# main.net
KiCad netlist of a schematic drawn in EAGLE
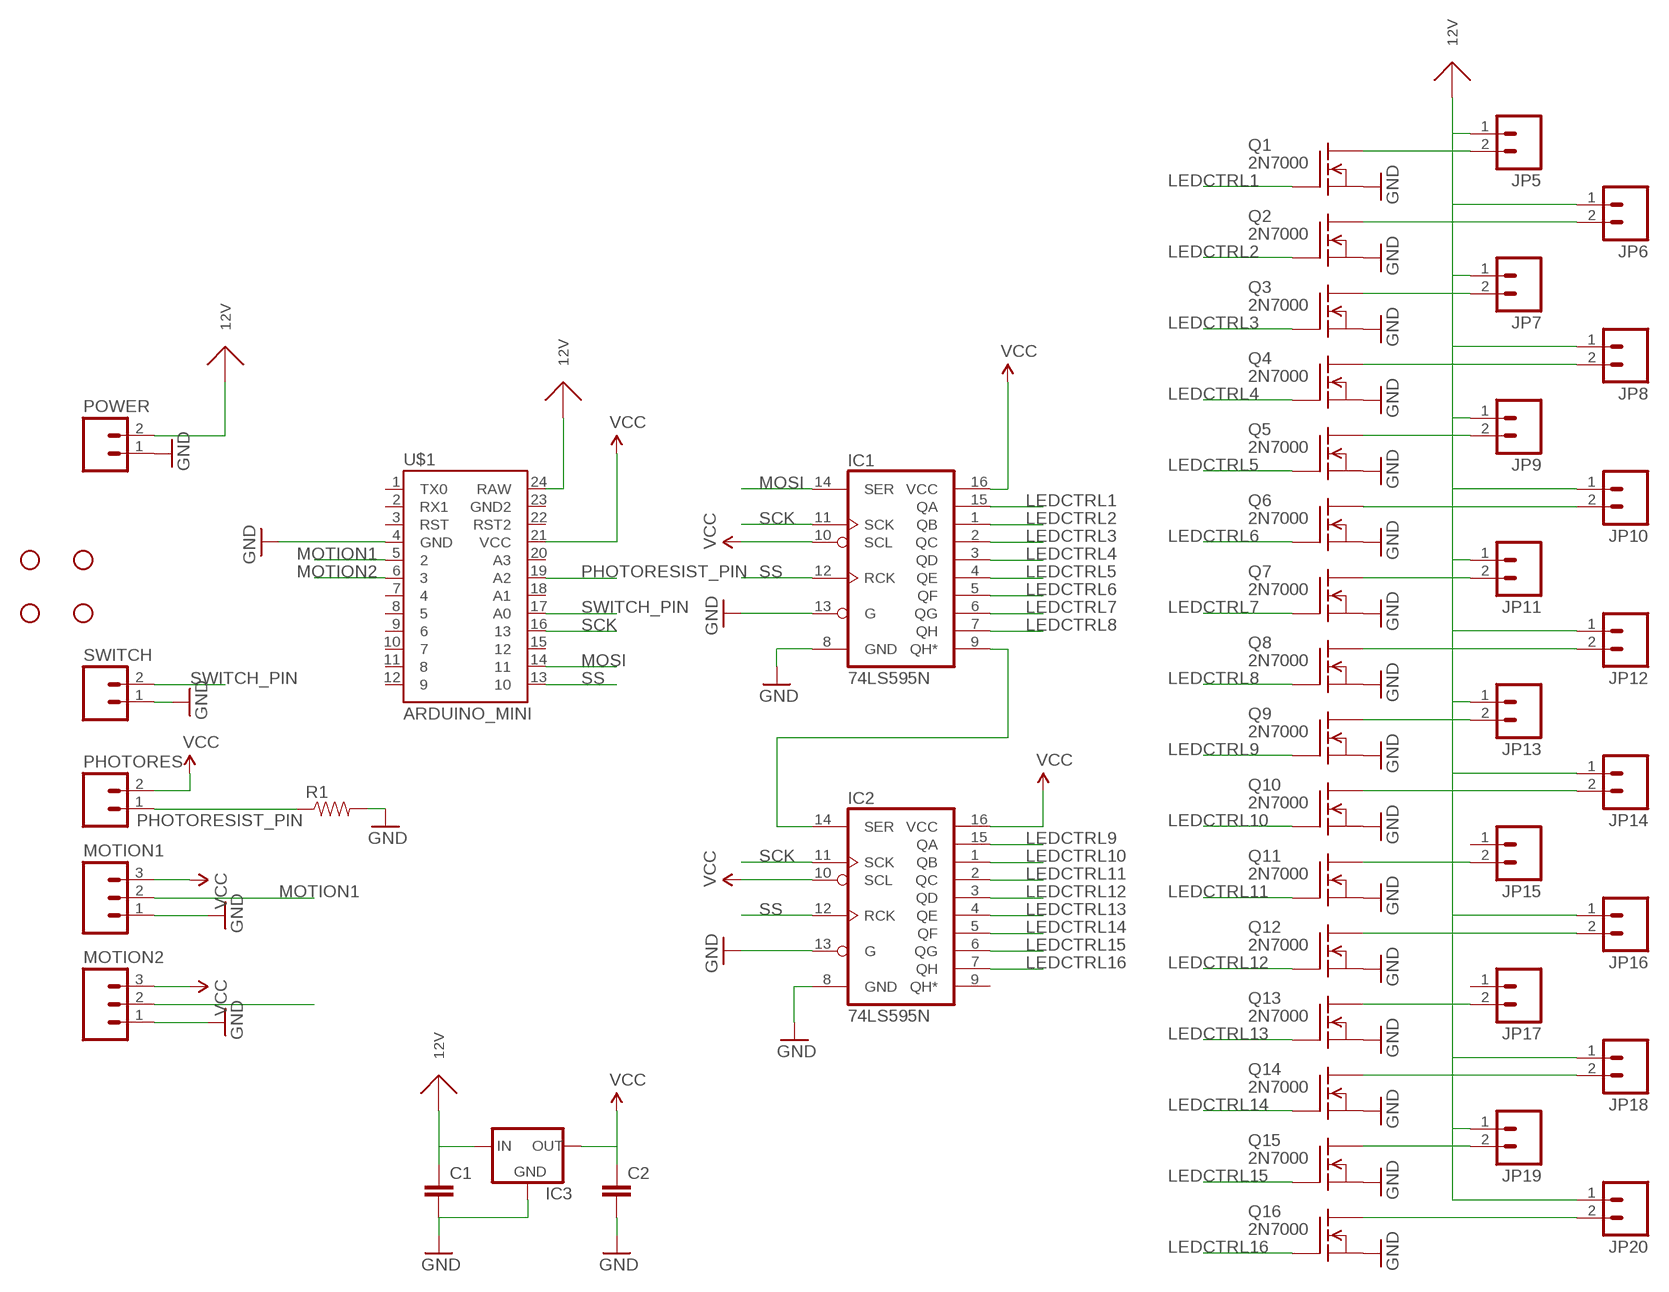
[diagram p0: schematic, sheet 1]

(export (version "E")
  (design (tool "Eeschema 10.0.6"))
  (components
    (comp (ref "C1")
      (value "CAPKIT")
      (footprint "eagle-import:CAP-PTH-SMALL-KIT")
      (libsource (lib "eagle-import") (part "CAPKIT"))
    )
    (comp (ref "C2")
      (value "CAPKIT")
      (footprint "eagle-import:CAP-PTH-SMALL-KIT")
      (libsource (lib "eagle-import") (part "CAPKIT"))
    )
    (comp (ref "IC1")
      (value "74LS595N")
      (footprint "eagle-import:DIL16")
      (libsource (lib "eagle-import") (part "74595NLS"))
    )
    (comp (ref "IC2")
      (value "74LS595N")
      (footprint "eagle-import:DIL16")
      (libsource (lib "eagle-import") (part "74595NLS"))
    )
    (comp (ref "IC3")
      (value "V_REG_78XXSINK")
      (footprint "eagle-import:TO220-IGO")
      (libsource (lib "eagle-import") (part "V_REG_78XXSINK"))
    )
    (comp (ref "JP1")
      (value "STAND-OFF")
      (footprint "eagle-import:STAND-OFF")
      (libsource (lib "eagle-import") (part "STAND-OFF"))
    )
    (comp (ref "JP2")
      (value "STAND-OFF")
      (footprint "eagle-import:STAND-OFF")
      (libsource (lib "eagle-import") (part "STAND-OFF"))
    )
    (comp (ref "JP3")
      (value "STAND-OFF")
      (footprint "eagle-import:STAND-OFF")
      (libsource (lib "eagle-import") (part "STAND-OFF"))
    )
    (comp (ref "JP4")
      (value "STAND-OFF")
      (footprint "eagle-import:STAND-OFF")
      (libsource (lib "eagle-import") (part "STAND-OFF"))
    )
    (comp (ref "JP5")
      (value "M02PTH")
      (footprint "eagle-import:1X02")
      (libsource (lib "eagle-import") (part "M02PTH"))
    )
    (comp (ref "JP6")
      (value "M02PTH")
      (footprint "eagle-import:1X02")
      (libsource (lib "eagle-import") (part "M02PTH"))
    )
    (comp (ref "JP7")
      (value "M02PTH")
      (footprint "eagle-import:1X02")
      (libsource (lib "eagle-import") (part "M02PTH"))
    )
    (comp (ref "JP8")
      (value "M02PTH")
      (footprint "eagle-import:1X02")
      (libsource (lib "eagle-import") (part "M02PTH"))
    )
    (comp (ref "JP9")
      (value "M02PTH")
      (footprint "eagle-import:1X02")
      (libsource (lib "eagle-import") (part "M02PTH"))
    )
    (comp (ref "JP10")
      (value "M02PTH")
      (footprint "eagle-import:1X02")
      (libsource (lib "eagle-import") (part "M02PTH"))
    )
    (comp (ref "JP11")
      (value "M02PTH")
      (footprint "eagle-import:1X02")
      (libsource (lib "eagle-import") (part "M02PTH"))
    )
    (comp (ref "JP12")
      (value "M02PTH")
      (footprint "eagle-import:1X02")
      (libsource (lib "eagle-import") (part "M02PTH"))
    )
    (comp (ref "JP13")
      (value "M02PTH")
      (footprint "eagle-import:1X02")
      (libsource (lib "eagle-import") (part "M02PTH"))
    )
    (comp (ref "JP14")
      (value "M02PTH")
      (footprint "eagle-import:1X02")
      (libsource (lib "eagle-import") (part "M02PTH"))
    )
    (comp (ref "JP15")
      (value "M02PTH")
      (footprint "eagle-import:1X02")
      (libsource (lib "eagle-import") (part "M02PTH"))
    )
    (comp (ref "JP16")
      (value "M02PTH")
      (footprint "eagle-import:1X02")
      (libsource (lib "eagle-import") (part "M02PTH"))
    )
    (comp (ref "JP17")
      (value "M02PTH")
      (footprint "eagle-import:1X02")
      (libsource (lib "eagle-import") (part "M02PTH"))
    )
    (comp (ref "JP18")
      (value "M02PTH")
      (footprint "eagle-import:1X02")
      (libsource (lib "eagle-import") (part "M02PTH"))
    )
    (comp (ref "JP19")
      (value "M02PTH")
      (footprint "eagle-import:1X02")
      (libsource (lib "eagle-import") (part "M02PTH"))
    )
    (comp (ref "JP20")
      (value "M02PTH")
      (footprint "eagle-import:1X02")
      (libsource (lib "eagle-import") (part "M02PTH"))
    )
    (comp (ref "MOTION1")
      (value "M03PTH")
      (footprint "eagle-import:1X03")
      (libsource (lib "eagle-import") (part "M03PTH"))
    )
    (comp (ref "MOTION2")
      (value "M03PTH")
      (footprint "eagle-import:1X03")
      (libsource (lib "eagle-import") (part "M03PTH"))
    )
    (comp (ref "PHOTORES")
      (value "M02PTH")
      (footprint "eagle-import:1X02")
      (libsource (lib "eagle-import") (part "M02PTH"))
    )
    (comp (ref "POWER")
      (value "M025MM")
      (footprint "eagle-import:SCREWTERMINAL-5MM-2")
      (libsource (lib "eagle-import") (part "M025MM"))
    )
    (comp (ref "Q1")
      (value "2N7000")
      (footprint "eagle-import:TO92")
      (libsource (lib "eagle-import") (part "2N7000"))
    )
    (comp (ref "Q2")
      (value "2N7000")
      (footprint "eagle-import:TO92")
      (libsource (lib "eagle-import") (part "2N7000"))
    )
    (comp (ref "Q3")
      (value "2N7000")
      (footprint "eagle-import:TO92")
      (libsource (lib "eagle-import") (part "2N7000"))
    )
    (comp (ref "Q4")
      (value "2N7000")
      (footprint "eagle-import:TO92")
      (libsource (lib "eagle-import") (part "2N7000"))
    )
    (comp (ref "Q5")
      (value "2N7000")
      (footprint "eagle-import:TO92")
      (libsource (lib "eagle-import") (part "2N7000"))
    )
    (comp (ref "Q6")
      (value "2N7000")
      (footprint "eagle-import:TO92")
      (libsource (lib "eagle-import") (part "2N7000"))
    )
    (comp (ref "Q7")
      (value "2N7000")
      (footprint "eagle-import:TO92")
      (libsource (lib "eagle-import") (part "2N7000"))
    )
    (comp (ref "Q8")
      (value "2N7000")
      (footprint "eagle-import:TO92")
      (libsource (lib "eagle-import") (part "2N7000"))
    )
    (comp (ref "Q9")
      (value "2N7000")
      (footprint "eagle-import:TO92")
      (libsource (lib "eagle-import") (part "2N7000"))
    )
    (comp (ref "Q10")
      (value "2N7000")
      (footprint "eagle-import:TO92")
      (libsource (lib "eagle-import") (part "2N7000"))
    )
    (comp (ref "Q11")
      (value "2N7000")
      (footprint "eagle-import:TO92")
      (libsource (lib "eagle-import") (part "2N7000"))
    )
    (comp (ref "Q12")
      (value "2N7000")
      (footprint "eagle-import:TO92")
      (libsource (lib "eagle-import") (part "2N7000"))
    )
    (comp (ref "Q13")
      (value "2N7000")
      (footprint "eagle-import:TO92")
      (libsource (lib "eagle-import") (part "2N7000"))
    )
    (comp (ref "Q14")
      (value "2N7000")
      (footprint "eagle-import:TO92")
      (libsource (lib "eagle-import") (part "2N7000"))
    )
    (comp (ref "Q15")
      (value "2N7000")
      (footprint "eagle-import:TO92")
      (libsource (lib "eagle-import") (part "2N7000"))
    )
    (comp (ref "Q16")
      (value "2N7000")
      (footprint "eagle-import:TO92")
      (libsource (lib "eagle-import") (part "2N7000"))
    )
    (comp (ref "R1")
      (value "RESISTORAXIAL-0.3")
      (footprint "eagle-import:AXIAL-0.3")
      (libsource (lib "eagle-import") (part "RESISTORAXIAL-0.3"))
    )
    (comp (ref "SWITCH")
      (value "M02PTH")
      (footprint "eagle-import:1X02")
      (libsource (lib "eagle-import") (part "M02PTH"))
    )
    (comp (ref "U$1")
      (value "ARDUINO_MINI")
      (footprint "eagle-import:ARDUINO_MINI")
      (libsource (lib "eagle-import") (part "ARDUINO_MINI"))
    )
  )
  (nets
    (net (code "1") (name "/LEDCTRL1") (class "Default")
      (node (ref "IC1") (pin "15") (pinfunction "QA_15") (pintype "tri_state"))
      (node (ref "Q1") (pin "2") (pinfunction "G_2") (pintype "passive"))
    )
    (net (code "2") (name "/LEDCTRL2") (class "Default")
      (node (ref "IC1") (pin "1") (pinfunction "QB_1") (pintype "tri_state"))
      (node (ref "Q2") (pin "2") (pinfunction "G_2") (pintype "passive"))
    )
    (net (code "3") (name "/LEDCTRL3") (class "Default")
      (node (ref "IC1") (pin "2") (pinfunction "QC_2") (pintype "tri_state"))
      (node (ref "Q3") (pin "2") (pinfunction "G_2") (pintype "passive"))
    )
    (net (code "4") (name "/LEDCTRL4") (class "Default")
      (node (ref "IC1") (pin "3") (pinfunction "QD_3") (pintype "tri_state"))
      (node (ref "Q4") (pin "2") (pinfunction "G_2") (pintype "passive"))
    )
    (net (code "5") (name "/LEDCTRL5") (class "Default")
      (node (ref "IC1") (pin "4") (pinfunction "QE_4") (pintype "tri_state"))
      (node (ref "Q5") (pin "2") (pinfunction "G_2") (pintype "passive"))
    )
    (net (code "6") (name "/LEDCTRL6") (class "Default")
      (node (ref "IC1") (pin "5") (pinfunction "QF_5") (pintype "tri_state"))
      (node (ref "Q6") (pin "2") (pinfunction "G_2") (pintype "passive"))
    )
    (net (code "7") (name "/LEDCTRL7") (class "Default")
      (node (ref "IC1") (pin "6") (pinfunction "QG_6") (pintype "tri_state"))
      (node (ref "Q7") (pin "2") (pinfunction "G_2") (pintype "passive"))
    )
    (net (code "8") (name "/LEDCTRL8") (class "Default")
      (node (ref "IC1") (pin "7") (pinfunction "QH_7") (pintype "tri_state"))
      (node (ref "Q8") (pin "2") (pinfunction "G_2") (pintype "passive"))
    )
    (net (code "9") (name "/LEDCTRL9") (class "Default")
      (node (ref "IC2") (pin "15") (pinfunction "QA_15") (pintype "tri_state"))
      (node (ref "Q9") (pin "2") (pinfunction "G_2") (pintype "passive"))
    )
    (net (code "10") (name "/LEDCTRL10") (class "Default")
      (node (ref "IC2") (pin "1") (pinfunction "QB_1") (pintype "tri_state"))
      (node (ref "Q10") (pin "2") (pinfunction "G_2") (pintype "passive"))
    )
    (net (code "11") (name "/LEDCTRL11") (class "Default")
      (node (ref "IC2") (pin "2") (pinfunction "QC_2") (pintype "tri_state"))
      (node (ref "Q11") (pin "2") (pinfunction "G_2") (pintype "passive"))
    )
    (net (code "12") (name "/LEDCTRL12") (class "Default")
      (node (ref "IC2") (pin "3") (pinfunction "QD_3") (pintype "tri_state"))
      (node (ref "Q12") (pin "2") (pinfunction "G_2") (pintype "passive"))
    )
    (net (code "13") (name "/LEDCTRL13") (class "Default")
      (node (ref "IC2") (pin "4") (pinfunction "QE_4") (pintype "tri_state"))
      (node (ref "Q13") (pin "2") (pinfunction "G_2") (pintype "passive"))
    )
    (net (code "14") (name "/LEDCTRL14") (class "Default")
      (node (ref "IC2") (pin "5") (pinfunction "QF_5") (pintype "tri_state"))
      (node (ref "Q14") (pin "2") (pinfunction "G_2") (pintype "passive"))
    )
    (net (code "15") (name "/LEDCTRL15") (class "Default")
      (node (ref "IC2") (pin "6") (pinfunction "QG_6") (pintype "tri_state"))
      (node (ref "Q15") (pin "2") (pinfunction "G_2") (pintype "passive"))
    )
    (net (code "16") (name "/LEDCTRL16") (class "Default")
      (node (ref "IC2") (pin "7") (pinfunction "QH_7") (pintype "tri_state"))
      (node (ref "Q16") (pin "2") (pinfunction "G_2") (pintype "passive"))
    )
    (net (code "17") (name "/MOSI") (class "Default")
      (node (ref "IC1") (pin "14") (pinfunction "SER_14") (pintype "input"))
      (node (ref "U$1") (pin "14") (pinfunction "11_14") (pintype "bidirectional"))
    )
    (net (code "18") (name "/MOTION1") (class "Default")
      (node (ref "MOTION1") (pin "2") (pinfunction "2_2") (pintype "passive"))
      (node (ref "U$1") (pin "5") (pinfunction "2_5") (pintype "bidirectional"))
    )
    (net (code "19") (name "/MOTION2") (class "Default")
      (node (ref "MOTION2") (pin "2") (pinfunction "2_2") (pintype "passive"))
      (node (ref "U$1") (pin "6") (pinfunction "3_6") (pintype "bidirectional"))
    )
    (net (code "20") (name "/PHOTORESIST_PIN") (class "Default")
      (node (ref "PHOTORES") (pin "1") (pinfunction "1_1") (pintype "passive"))
      (node (ref "R1") (pin "P$1") (pinfunction "1_P$1") (pintype "passive"))
      (node (ref "U$1") (pin "19") (pinfunction "A2_19") (pintype "bidirectional"))
    )
    (net (code "21") (name "/SCK") (class "Default")
      (node (ref "IC1") (pin "11") (pinfunction "SCK_11") (pintype "input"))
      (node (ref "IC2") (pin "11") (pinfunction "SCK_11") (pintype "input"))
      (node (ref "U$1") (pin "16") (pinfunction "13_16") (pintype "bidirectional"))
    )
    (net (code "22") (name "/SS") (class "Default")
      (node (ref "IC1") (pin "12") (pinfunction "RCK_12") (pintype "input"))
      (node (ref "IC2") (pin "12") (pinfunction "RCK_12") (pintype "input"))
      (node (ref "U$1") (pin "13") (pinfunction "10_13") (pintype "bidirectional"))
    )
    (net (code "23") (name "/SWITCH_PIN") (class "Default")
      (node (ref "SWITCH") (pin "2") (pinfunction "2_2") (pintype "passive"))
      (node (ref "U$1") (pin "17") (pinfunction "A0_17") (pintype "bidirectional"))
    )
    (net (code "24") (name "12V") (class "Default")
      (node (ref "C1") (pin "1") (pinfunction "1_1") (pintype "passive"))
      (node (ref "IC3") (pin "IN") (pinfunction "IN_IN") (pintype "input"))
      (node (ref "JP10") (pin "1") (pinfunction "1_1") (pintype "passive"))
      (node (ref "JP11") (pin "1") (pinfunction "1_1") (pintype "passive"))
      (node (ref "JP12") (pin "1") (pinfunction "1_1") (pintype "passive"))
      (node (ref "JP13") (pin "1") (pinfunction "1_1") (pintype "passive"))
      (node (ref "JP14") (pin "1") (pinfunction "1_1") (pintype "passive"))
      (node (ref "JP16") (pin "1") (pinfunction "1_1") (pintype "passive"))
      (node (ref "JP18") (pin "1") (pinfunction "1_1") (pintype "passive"))
      (node (ref "JP19") (pin "1") (pinfunction "1_1") (pintype "passive"))
      (node (ref "JP20") (pin "1") (pinfunction "1_1") (pintype "passive"))
      (node (ref "JP5") (pin "1") (pinfunction "1_1") (pintype "passive"))
      (node (ref "JP6") (pin "1") (pinfunction "1_1") (pintype "passive"))
      (node (ref "JP7") (pin "1") (pinfunction "1_1") (pintype "passive"))
      (node (ref "JP8") (pin "1") (pinfunction "1_1") (pintype "passive"))
      (node (ref "JP9") (pin "1") (pinfunction "1_1") (pintype "passive"))
      (node (ref "POWER") (pin "2") (pinfunction "2_2") (pintype "passive"))
      (node (ref "U$1") (pin "24") (pinfunction "RAW_24") (pintype "bidirectional"))
    )
    (net (code "25") (name "GND") (class "Default")
      (node (ref "C1") (pin "2") (pinfunction "2_2") (pintype "passive"))
      (node (ref "C2") (pin "2") (pinfunction "2_2") (pintype "passive"))
      (node (ref "IC1") (pin "13") (pinfunction "G_13") (pintype "input"))
      (node (ref "IC1") (pin "8") (pinfunction "GND_8") (pintype "power_in"))
      (node (ref "IC2") (pin "13") (pinfunction "G_13") (pintype "input"))
      (node (ref "IC2") (pin "8") (pinfunction "GND_8") (pintype "power_in"))
      (node (ref "IC3") (pin "GND") (pinfunction "GND_GND") (pintype "input"))
      (node (ref "MOTION1") (pin "1") (pinfunction "1_1") (pintype "passive"))
      (node (ref "MOTION2") (pin "1") (pinfunction "1_1") (pintype "passive"))
      (node (ref "POWER") (pin "1") (pinfunction "1_1") (pintype "passive"))
      (node (ref "Q1") (pin "1") (pinfunction "S_1") (pintype "passive"))
      (node (ref "Q10") (pin "1") (pinfunction "S_1") (pintype "passive"))
      (node (ref "Q11") (pin "1") (pinfunction "S_1") (pintype "passive"))
      (node (ref "Q12") (pin "1") (pinfunction "S_1") (pintype "passive"))
      (node (ref "Q13") (pin "1") (pinfunction "S_1") (pintype "passive"))
      (node (ref "Q14") (pin "1") (pinfunction "S_1") (pintype "passive"))
      (node (ref "Q15") (pin "1") (pinfunction "S_1") (pintype "passive"))
      (node (ref "Q16") (pin "1") (pinfunction "S_1") (pintype "passive"))
      (node (ref "Q2") (pin "1") (pinfunction "S_1") (pintype "passive"))
      (node (ref "Q3") (pin "1") (pinfunction "S_1") (pintype "passive"))
      (node (ref "Q4") (pin "1") (pinfunction "S_1") (pintype "passive"))
      (node (ref "Q5") (pin "1") (pinfunction "S_1") (pintype "passive"))
      (node (ref "Q6") (pin "1") (pinfunction "S_1") (pintype "passive"))
      (node (ref "Q7") (pin "1") (pinfunction "S_1") (pintype "passive"))
      (node (ref "Q8") (pin "1") (pinfunction "S_1") (pintype "passive"))
      (node (ref "Q9") (pin "1") (pinfunction "S_1") (pintype "passive"))
      (node (ref "R1") (pin "P$2") (pinfunction "2_P$2") (pintype "passive"))
      (node (ref "SWITCH") (pin "1") (pinfunction "1_1") (pintype "passive"))
      (node (ref "U$1") (pin "4") (pinfunction "GND_4") (pintype "bidirectional"))
    )
    (net (code "26") (name "Net-(IC1-QH*)") (class "Default")
      (node (ref "IC1") (pin "9") (pinfunction "QH*_9") (pintype "tri_state"))
      (node (ref "IC2") (pin "14") (pinfunction "SER_14") (pintype "input"))
    )
    (net (code "27") (name "Net-(Q1-D)") (class "Default")
      (node (ref "JP5") (pin "2") (pinfunction "2_2") (pintype "passive"))
      (node (ref "Q1") (pin "3") (pinfunction "D_3") (pintype "passive"))
    )
    (net (code "28") (name "Net-(Q2-D)") (class "Default")
      (node (ref "JP6") (pin "2") (pinfunction "2_2") (pintype "passive"))
      (node (ref "Q2") (pin "3") (pinfunction "D_3") (pintype "passive"))
    )
    (net (code "29") (name "Net-(Q3-D)") (class "Default")
      (node (ref "JP7") (pin "2") (pinfunction "2_2") (pintype "passive"))
      (node (ref "Q3") (pin "3") (pinfunction "D_3") (pintype "passive"))
    )
    (net (code "30") (name "Net-(Q4-D)") (class "Default")
      (node (ref "JP8") (pin "2") (pinfunction "2_2") (pintype "passive"))
      (node (ref "Q4") (pin "3") (pinfunction "D_3") (pintype "passive"))
    )
    (net (code "31") (name "Net-(Q5-D)") (class "Default")
      (node (ref "JP9") (pin "2") (pinfunction "2_2") (pintype "passive"))
      (node (ref "Q5") (pin "3") (pinfunction "D_3") (pintype "passive"))
    )
    (net (code "32") (name "Net-(Q6-D)") (class "Default")
      (node (ref "JP10") (pin "2") (pinfunction "2_2") (pintype "passive"))
      (node (ref "Q6") (pin "3") (pinfunction "D_3") (pintype "passive"))
    )
    (net (code "33") (name "Net-(Q7-D)") (class "Default")
      (node (ref "JP11") (pin "2") (pinfunction "2_2") (pintype "passive"))
      (node (ref "Q7") (pin "3") (pinfunction "D_3") (pintype "passive"))
    )
    (net (code "34") (name "Net-(Q8-D)") (class "Default")
      (node (ref "JP12") (pin "2") (pinfunction "2_2") (pintype "passive"))
      (node (ref "Q8") (pin "3") (pinfunction "D_3") (pintype "passive"))
    )
    (net (code "35") (name "Net-(Q9-D)") (class "Default")
      (node (ref "JP13") (pin "2") (pinfunction "2_2") (pintype "passive"))
      (node (ref "Q9") (pin "3") (pinfunction "D_3") (pintype "passive"))
    )
    (net (code "36") (name "Net-(Q10-D)") (class "Default")
      (node (ref "JP14") (pin "2") (pinfunction "2_2") (pintype "passive"))
      (node (ref "Q10") (pin "3") (pinfunction "D_3") (pintype "passive"))
    )
    (net (code "37") (name "Net-(Q11-D)") (class "Default")
      (node (ref "JP15") (pin "2") (pinfunction "2_2") (pintype "passive"))
      (node (ref "Q11") (pin "3") (pinfunction "D_3") (pintype "passive"))
    )
    (net (code "38") (name "Net-(Q12-D)") (class "Default")
      (node (ref "JP16") (pin "2") (pinfunction "2_2") (pintype "passive"))
      (node (ref "Q12") (pin "3") (pinfunction "D_3") (pintype "passive"))
    )
    (net (code "39") (name "Net-(Q13-D)") (class "Default")
      (node (ref "JP17") (pin "2") (pinfunction "2_2") (pintype "passive"))
      (node (ref "Q13") (pin "3") (pinfunction "D_3") (pintype "passive"))
    )
    (net (code "40") (name "Net-(Q14-D)") (class "Default")
      (node (ref "JP18") (pin "2") (pinfunction "2_2") (pintype "passive"))
      (node (ref "Q14") (pin "3") (pinfunction "D_3") (pintype "passive"))
    )
    (net (code "41") (name "Net-(Q15-D)") (class "Default")
      (node (ref "JP19") (pin "2") (pinfunction "2_2") (pintype "passive"))
      (node (ref "Q15") (pin "3") (pinfunction "D_3") (pintype "passive"))
    )
    (net (code "42") (name "Net-(Q16-D)") (class "Default")
      (node (ref "JP20") (pin "2") (pinfunction "2_2") (pintype "passive"))
      (node (ref "Q16") (pin "3") (pinfunction "D_3") (pintype "passive"))
    )
    (net (code "43") (name "VCC") (class "Default")
      (node (ref "C2") (pin "1") (pinfunction "1_1") (pintype "passive"))
      (node (ref "IC1") (pin "10") (pinfunction "SCL_10") (pintype "input"))
      (node (ref "IC1") (pin "16") (pinfunction "VCC_16") (pintype "power_in"))
      (node (ref "IC2") (pin "10") (pinfunction "SCL_10") (pintype "input"))
      (node (ref "IC2") (pin "16") (pinfunction "VCC_16") (pintype "power_in"))
      (node (ref "IC3") (pin "OUT") (pinfunction "OUT_OUT") (pintype "output"))
      (node (ref "MOTION1") (pin "3") (pinfunction "3_3") (pintype "passive"))
      (node (ref "MOTION2") (pin "3") (pinfunction "3_3") (pintype "passive"))
      (node (ref "PHOTORES") (pin "2") (pinfunction "2_2") (pintype "passive"))
      (node (ref "U$1") (pin "21") (pinfunction "VCC_21") (pintype "bidirectional"))
    )
    (net (code "44") (name "unconnected-(IC2-QH*-Pad9)") (class "Default")
      (node (ref "IC2") (pin "9") (pinfunction "QH*_9") (pintype "tri_state"))
    )
    (net (code "45") (name "unconnected-(JP15-Pad1)") (class "Default")
      (node (ref "JP15") (pin "1") (pinfunction "1_1") (pintype "passive"))
    )
    (net (code "46") (name "unconnected-(JP17-Pad1)") (class "Default")
      (node (ref "JP17") (pin "1") (pinfunction "1_1") (pintype "passive"))
    )
    (net (code "47") (name "unconnected-(U$1-4-Pad7)") (class "Default")
      (node (ref "U$1") (pin "7") (pinfunction "4_7") (pintype "bidirectional"))
    )
    (net (code "48") (name "unconnected-(U$1-5-Pad8)") (class "Default")
      (node (ref "U$1") (pin "8") (pinfunction "5_8") (pintype "bidirectional"))
    )
    (net (code "49") (name "unconnected-(U$1-6-Pad9)") (class "Default")
      (node (ref "U$1") (pin "9") (pinfunction "6_9") (pintype "bidirectional"))
    )
    (net (code "50") (name "unconnected-(U$1-7-Pad10)") (class "Default")
      (node (ref "U$1") (pin "10") (pinfunction "7_10") (pintype "bidirectional"))
    )
    (net (code "51") (name "unconnected-(U$1-8-Pad11)") (class "Default")
      (node (ref "U$1") (pin "11") (pinfunction "8_11") (pintype "bidirectional"))
    )
    (net (code "52") (name "unconnected-(U$1-9-Pad12)") (class "Default")
      (node (ref "U$1") (pin "12") (pinfunction "9_12") (pintype "bidirectional"))
    )
    (net (code "53") (name "unconnected-(U$1-12-Pad15)") (class "Default")
      (node (ref "U$1") (pin "15") (pinfunction "12_15") (pintype "bidirectional"))
    )
    (net (code "54") (name "unconnected-(U$1-A1-Pad18)") (class "Default")
      (node (ref "U$1") (pin "18") (pinfunction "A1_18") (pintype "bidirectional"))
    )
    (net (code "55") (name "unconnected-(U$1-A3-Pad20)") (class "Default")
      (node (ref "U$1") (pin "20") (pinfunction "A3_20") (pintype "bidirectional"))
    )
    (net (code "56") (name "unconnected-(U$1-GND2-Pad23)") (class "Default")
      (node (ref "U$1") (pin "23") (pinfunction "GND2_23") (pintype "bidirectional"))
    )
    (net (code "57") (name "unconnected-(U$1-RST-Pad3)") (class "Default")
      (node (ref "U$1") (pin "3") (pinfunction "RST_3") (pintype "bidirectional"))
    )
    (net (code "58") (name "unconnected-(U$1-RST2-Pad22)") (class "Default")
      (node (ref "U$1") (pin "22") (pinfunction "RST2_22") (pintype "bidirectional"))
    )
    (net (code "59") (name "unconnected-(U$1-RX1-Pad2)") (class "Default")
      (node (ref "U$1") (pin "2") (pinfunction "RX1_2") (pintype "bidirectional"))
    )
    (net (code "60") (name "unconnected-(U$1-TX0-Pad1)") (class "Default")
      (node (ref "U$1") (pin "1") (pinfunction "TX0_1") (pintype "bidirectional"))
    )
  )
)
